# SCH_Smart_Home_2023-06-21.net
KiCad netlist of a schematic drawn in EasyEDA
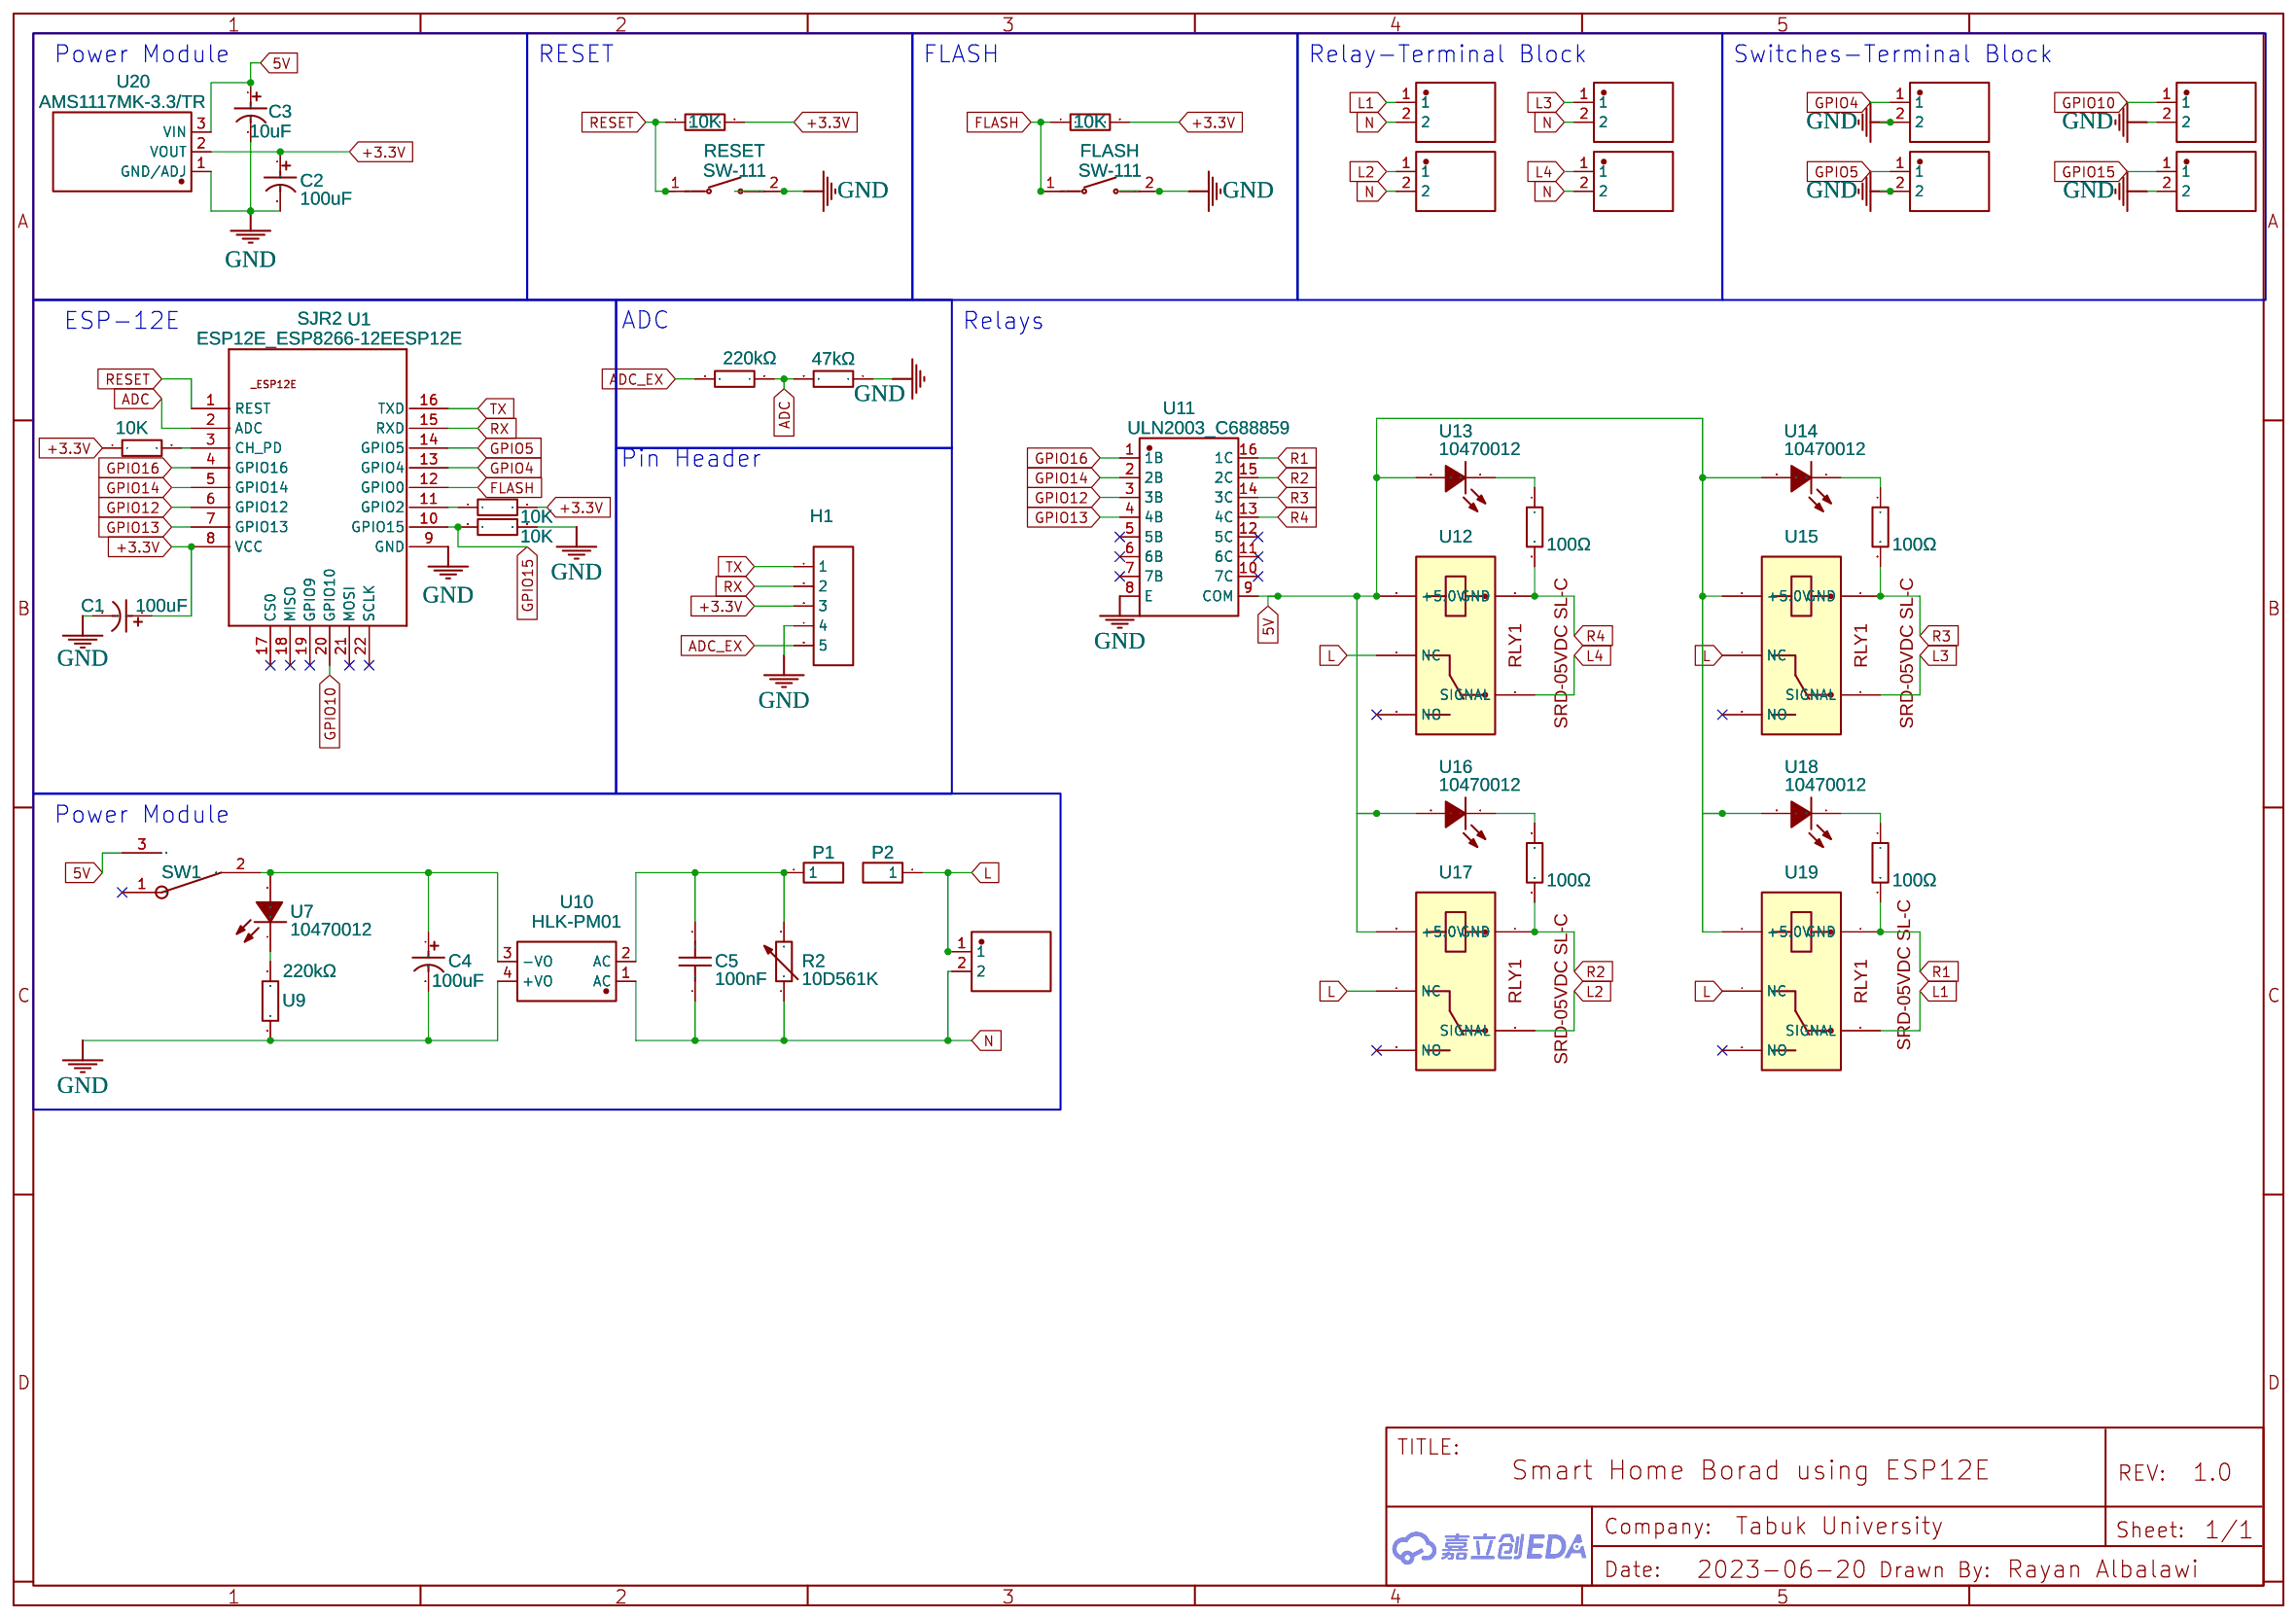
[diagram p0: schematic sheet]

(export (version "E")
  (design (tool "Eeschema 10.0.6"))
  (components
    (comp (ref "C1")
      (value "100uF")
      (fields
        (field (name "BOM_Manufacturer Part") "100uF 35V 6.3*11")
        (field (name "BOM_Supplier Part") "C45076")
      )
      (libsource (lib "") (part "100uF 35V 6.3*11_C45076_1"))
    )
    (comp (ref "C2")
      (value "100uF")
      (fields
        (field (name "BOM_Manufacturer Part") "100uF 35V 6.3*11")
        (field (name "BOM_Supplier Part") "C45076")
      )
      (libsource (lib "") (part "100uF 35V 6.3*11_C45076"))
    )
    (comp (ref "C3")
      (value "10uF")
      (fields
        (field (name "BOM_Manufacturer Part") "100uF 35V 6.3*11")
        (field (name "BOM_Supplier Part") "C45076")
      )
      (libsource (lib "") (part "100uF 35V 6.3*11_C45076"))
    )
    (comp (ref "C4")
      (value "100uF")
      (fields
        (field (name "BOM_Manufacturer Part") "100uF 35V 6.3*11")
        (field (name "BOM_Supplier Part") "C45076")
      )
      (libsource (lib "") (part "100uF 35V 6.3*11_C45076"))
    )
    (comp (ref "C5")
      (value "100nF")
      (fields
        (field (name "BOM_Manufacturer Part") "B32520C3104K000")
        (field (name "BOM_Supplier Part") "C125382")
      )
      (libsource (lib "") (part "B32520C3104K000"))
    )
    (comp (ref "CN1")
      (value "WJ127-5.0-2P_C187897")
      (fields
        (field (name "BOM_Manufacturer Part") "WJ127-5.0-2P")
        (field (name "BOM_Supplier Part") "C187897")
      )
      (libsource (lib "") (part "WJ127-5.0-2P_C187897"))
    )
    (comp (ref "CN2")
      (value "WJ127-5.0-2P_C187897")
      (fields
        (field (name "BOM_Manufacturer Part") "WJ127-5.0-2P")
        (field (name "BOM_Supplier Part") "C187897")
      )
      (libsource (lib "") (part "WJ127-5.0-2P_C187897"))
    )
    (comp (ref "CN3")
      (value "WJ127-5.0-2P_C187897")
      (fields
        (field (name "BOM_Manufacturer Part") "WJ127-5.0-2P")
        (field (name "BOM_Supplier Part") "C187897")
      )
      (libsource (lib "") (part "WJ127-5.0-2P_C187897"))
    )
    (comp (ref "CN4")
      (value "WJ127-5.0-2P_C187897")
      (fields
        (field (name "BOM_Manufacturer Part") "WJ127-5.0-2P")
        (field (name "BOM_Supplier Part") "C187897")
      )
      (libsource (lib "") (part "WJ127-5.0-2P_C187897"))
    )
    (comp (ref "CN5")
      (value "WJ127-5.0-2P_C187897")
      (fields
        (field (name "BOM_Manufacturer Part") "WJ127-5.0-2P")
        (field (name "BOM_Supplier Part") "C187897")
      )
      (libsource (lib "") (part "WJ127-5.0-2P_C187897"))
    )
    (comp (ref "CN6")
      (value "WJ127-5.0-2P_C187897")
      (fields
        (field (name "BOM_Manufacturer Part") "WJ127-5.0-2P")
        (field (name "BOM_Supplier Part") "C187897")
      )
      (libsource (lib "") (part "WJ127-5.0-2P_C187897"))
    )
    (comp (ref "CN7")
      (value "WJ127-5.0-2P_C187897")
      (fields
        (field (name "BOM_Manufacturer Part") "WJ127-5.0-2P")
        (field (name "BOM_Supplier Part") "C187897")
      )
      (libsource (lib "") (part "WJ127-5.0-2P_C187897"))
    )
    (comp (ref "CN8")
      (value "WJ127-5.0-2P_C187897")
      (fields
        (field (name "BOM_Manufacturer Part") "WJ127-5.0-2P")
        (field (name "BOM_Supplier Part") "C187897")
      )
      (libsource (lib "") (part "WJ127-5.0-2P_C187897"))
    )
    (comp (ref "CN9")
      (value "WJ127-5.0-2P_C187897")
      (fields
        (field (name "BOM_Manufacturer Part") "WJ127-5.0-2P")
        (field (name "BOM_Supplier Part") "C187897")
      )
      (libsource (lib "") (part "WJ127-5.0-2P_C187897"))
    )
    (comp (ref "FLASH")
      (value "SW-111")
      (fields (field (name "BOM_Supplier Part") "C294475"))
      (libsource (lib "") (part "SW-111"))
    )
    (comp (ref "H1")
      (value "Header-Female-2.54_1x5")
      (fields (field (name "BOM_Manufacturer Part") "2.54-1*5P母") (field (name "BOM_Supplier Part") "C50950"))
      (libsource (lib "") (part "Header-Female-2.54_1x5"))
    )
    (comp (ref "P1")
      (value "Header-Male-2.54_1x1")
      (fields (field (name "BOM_Manufacturer Part") "2.54-1*1P针") (field (name "BOM_Supplier Part") "C81276"))
      (libsource (lib "") (part "Header-Male-2.54_1x1"))
    )
    (comp (ref "P2")
      (value "Header-Male-2.54_1x1")
      (fields (field (name "BOM_Manufacturer Part") "2.54-1*1P针") (field (name "BOM_Supplier Part") "C81276"))
      (libsource (lib "") (part "Header-Male-2.54_1x1_1"))
    )
    (comp (ref "R1")
      (value "47kΩ")
      (fields
        (field (name "BOM_Manufacturer Part") "MOF2WS-47KΩ±5% T")
        (field (name "BOM_Supplier Part") "C121703")
      )
      (libsource (lib "") (part "MOF2WS-47KΩ±5% T_1"))
    )
    (comp (ref "R2")
      (value "10D561K")
      (fields (field (name "BOM_Supplier Part") "C113236"))
      (libsource (lib "") (part "10D561K"))
    )
    (comp (ref "R3")
      (value "100Ω")
      (fields
        (field (name "BOM_Manufacturer Part") "MOF2WS-47KΩ±5% T")
        (field (name "BOM_Supplier Part") "C121703")
      )
      (libsource (lib "") (part "MOF2WS-47KΩ±5% T"))
    )
    (comp (ref "R4")
      (value "100Ω")
      (fields
        (field (name "BOM_Manufacturer Part") "MOF2WS-47KΩ±5% T")
        (field (name "BOM_Supplier Part") "C121703")
      )
      (libsource (lib "") (part "MOF2WS-47KΩ±5% T"))
    )
    (comp (ref "R5")
      (value "100Ω")
      (fields
        (field (name "BOM_Manufacturer Part") "MOF2WS-47KΩ±5% T")
        (field (name "BOM_Supplier Part") "C121703")
      )
      (libsource (lib "") (part "MOF2WS-47KΩ±5% T"))
    )
    (comp (ref "R6")
      (value "100Ω")
      (fields
        (field (name "BOM_Manufacturer Part") "MOF2WS-47KΩ±5% T")
        (field (name "BOM_Supplier Part") "C121703")
      )
      (libsource (lib "") (part "MOF2WS-47KΩ±5% T"))
    )
    (comp (ref "RESET")
      (value "SW-111")
      (fields (field (name "BOM_Supplier Part") "C294475"))
      (libsource (lib "") (part "SW-111_1"))
    )
    (comp (ref "SJR2")
      (value "ESP12E_ESP8266-12EESP12E")
      (libsource (lib "") (part "ESP12E_ESP8266-12EESP12E"))
    )
    (comp (ref "SW1")
      (value "EG1218")
      (fields (field (name "BOM_Supplier Part") "C273394"))
      (libsource (lib "") (part "EG1218"))
    )
    (comp (ref "U1")
      (value "10K")
      (fields
        (field (name "BOM_Manufacturer Part") "B3950-10K 1%")
        (field (name "BOM_Supplier Part") "C9900005609")
      )
      (libsource (lib "") (part "B3950-10K 1%"))
    )
    (comp (ref "U3")
      (value "10K")
      (fields
        (field (name "BOM_Manufacturer Part") "B3950-10K 1%")
        (field (name "BOM_Supplier Part") "C9900005609")
      )
      (libsource (lib "") (part "B3950-10K 1%"))
    )
    (comp (ref "U4")
      (value "10K")
      (fields
        (field (name "BOM_Manufacturer Part") "B3950-10K 1%")
        (field (name "BOM_Supplier Part") "C9900005609")
      )
      (libsource (lib "") (part "B3950-10K 1%"))
    )
    (comp (ref "U5")
      (value "10K")
      (fields
        (field (name "BOM_Manufacturer Part") "B3950-10K 1%")
        (field (name "BOM_Supplier Part") "C9900005609")
      )
      (libsource (lib "") (part "B3950-10K 1%"))
    )
    (comp (ref "U6")
      (value "10K")
      (fields
        (field (name "BOM_Manufacturer Part") "B3950-10K 1%")
        (field (name "BOM_Supplier Part") "C9900005609")
      )
      (libsource (lib "") (part "B3950-10K 1%"))
    )
    (comp (ref "U7")
      (value "10470012")
      (fields (field (name "BOM_Supplier Part") "C9900018803"))
      (libsource (lib "") (part "10470012_1"))
    )
    (comp (ref "U8")
      (value "220kΩ")
      (fields
        (field (name "BOM_Manufacturer Part") "MOF3WS-100KΩ±5% T")
        (field (name "BOM_Supplier Part") "C121880")
      )
      (libsource (lib "") (part "MOF3WS-100KΩ±5% T_1"))
    )
    (comp (ref "U9")
      (value "220kΩ")
      (fields
        (field (name "BOM_Manufacturer Part") "MOF3WS-100KΩ±5% T")
        (field (name "BOM_Supplier Part") "C121880")
      )
      (libsource (lib "") (part "MOF3WS-100KΩ±5% T"))
    )
    (comp (ref "U10")
      (value "HLK-PM01")
      (fields (field (name "BOM_Supplier Part") "C209903"))
      (libsource (lib "") (part "HLK-PM01"))
    )
    (comp (ref "U11")
      (value "ULN2003_C688859")
      (fields (field (name "BOM_Manufacturer Part") "ULN2003") (field (name "BOM_Supplier Part") "C688859"))
      (libsource (lib "") (part "ULN2003_C688859"))
    )
    (comp (ref "U12")
      (value "SRD-05VDC SL-C BY JMAD COPY")
      (fields (field (name "BOM_Supplier Part") "SRD-05VDC SL-C"))
      (libsource (lib "") (part "SRD-05VDC SL-C BY JMAD COPY"))
    )
    (comp (ref "U13")
      (value "10470012")
      (fields (field (name "BOM_Supplier Part") "C9900018803"))
      (libsource (lib "") (part "10470012"))
    )
    (comp (ref "U14")
      (value "10470012")
      (fields (field (name "BOM_Supplier Part") "C9900018803"))
      (libsource (lib "") (part "10470012"))
    )
    (comp (ref "U15")
      (value "SRD-05VDC SL-C BY JMAD COPY")
      (fields (field (name "BOM_Supplier Part") "SRD-05VDC SL-C"))
      (libsource (lib "") (part "SRD-05VDC SL-C BY JMAD COPY"))
    )
    (comp (ref "U16")
      (value "10470012")
      (fields (field (name "BOM_Supplier Part") "C9900018803"))
      (libsource (lib "") (part "10470012"))
    )
    (comp (ref "U17")
      (value "SRD-05VDC SL-C BY JMAD COPY")
      (fields (field (name "BOM_Supplier Part") "SRD-05VDC SL-C"))
      (libsource (lib "") (part "SRD-05VDC SL-C BY JMAD COPY"))
    )
    (comp (ref "U18")
      (value "10470012")
      (fields (field (name "BOM_Supplier Part") "C9900018803"))
      (libsource (lib "") (part "10470012"))
    )
    (comp (ref "U19")
      (value "SRD-05VDC SL-C BY JMAD COPY")
      (fields (field (name "BOM_Supplier Part") "SRD-05VDC SL-C"))
      (libsource (lib "") (part "SRD-05VDC SL-C BY JMAD COPY_1"))
    )
    (comp (ref "U20")
      (value "AMS1117MK-3.3/TR")
      (fields (field (name "BOM_Supplier Part") "C498147"))
      (libsource (lib "") (part "AMS1117MK-3.3/TR"))
    )
  )
  (nets
    (net (code "1") (name "+3.3V") (class "Default")
      (node (ref "C1") (pin "1") (pinfunction "1_1") (pintype "input"))
      (node (ref "C2") (pin "1") (pinfunction "1_1") (pintype "input"))
      (node (ref "H1") (pin "3") (pinfunction "3_3") (pintype "input"))
      (node (ref "SJR2") (pin "8") (pinfunction "VCC_8") (pintype "bidirectional"))
      (node (ref "U1") (pin "1") (pinfunction "1_1") (pintype "unspecified"))
      (node (ref "U20") (pin "2") (pinfunction "VOUT_2") (pintype "unspecified"))
      (node (ref "U3") (pin "2") (pinfunction "2_2") (pintype "unspecified"))
      (node (ref "U5") (pin "2") (pinfunction "2_2") (pintype "unspecified"))
      (node (ref "U6") (pin "2") (pinfunction "2_2") (pintype "unspecified"))
    )
    (net (code "2") (name "5V") (class "Default")
      (node (ref "C3") (pin "1") (pinfunction "1_1") (pintype "input"))
      (node (ref "SW1") (pin "3") (pinfunction "3_3") (pintype "input"))
      (node (ref "U11") (pin "9") (pinfunction "COM_9") (pintype "unspecified"))
      (node (ref "U12") (pin "2") (pinfunction "+5.0V_2") (pintype "passive"))
      (node (ref "U13") (pin "2") (pinfunction "A_2") (pintype "unspecified"))
      (node (ref "U14") (pin "2") (pinfunction "A_2") (pintype "unspecified"))
      (node (ref "U15") (pin "2") (pinfunction "+5.0V_2") (pintype "passive"))
      (node (ref "U16") (pin "2") (pinfunction "A_2") (pintype "unspecified"))
      (node (ref "U17") (pin "2") (pinfunction "+5.0V_2") (pintype "passive"))
      (node (ref "U18") (pin "2") (pinfunction "A_2") (pintype "unspecified"))
      (node (ref "U19") (pin "2") (pinfunction "+5.0V_2") (pintype "passive"))
      (node (ref "U20") (pin "3") (pinfunction "VIN_3") (pintype "unspecified"))
    )
    (net (code "3") (name "ADC") (class "Default")
      (node (ref "R1") (pin "2") (pinfunction "2_2") (pintype "unspecified"))
      (node (ref "SJR2") (pin "2") (pinfunction "ADC_2") (pintype "bidirectional"))
      (node (ref "U8") (pin "1") (pinfunction "1_1") (pintype "unspecified"))
    )
    (net (code "4") (name "ADC_EX") (class "Default")
      (node (ref "H1") (pin "5") (pinfunction "5_5") (pintype "input"))
      (node (ref "U8") (pin "2") (pinfunction "2_2") (pintype "unspecified"))
    )
    (net (code "5") (name "FLASH") (class "Default")
      (node (ref "FLASH") (pin "1") (pinfunction "1_1") (pintype "unspecified"))
      (node (ref "SJR2") (pin "12") (pinfunction "GPIO0_12") (pintype "bidirectional"))
      (node (ref "U6") (pin "1") (pinfunction "1_1") (pintype "unspecified"))
    )
    (net (code "6") (name "GND") (class "Default")
      (node (ref "C1") (pin "2") (pinfunction "2_2") (pintype "input"))
      (node (ref "C2") (pin "2") (pinfunction "2_2") (pintype "input"))
      (node (ref "C3") (pin "2") (pinfunction "2_2") (pintype "input"))
      (node (ref "C4") (pin "2") (pinfunction "2_2") (pintype "input"))
      (node (ref "CN5") (pin "2") (pinfunction "2_2") (pintype "unspecified"))
      (node (ref "CN6") (pin "2") (pinfunction "2_2") (pintype "unspecified"))
      (node (ref "CN7") (pin "2") (pinfunction "2_2") (pintype "unspecified"))
      (node (ref "CN8") (pin "2") (pinfunction "2_2") (pintype "unspecified"))
      (node (ref "FLASH") (pin "2") (pinfunction "2_2") (pintype "unspecified"))
      (node (ref "H1") (pin "4") (pinfunction "4_4") (pintype "input"))
      (node (ref "R1") (pin "1") (pinfunction "1_1") (pintype "unspecified"))
      (node (ref "RESET") (pin "2") (pinfunction "2_2") (pintype "unspecified"))
      (node (ref "SJR2") (pin "9") (pinfunction "GND_9") (pintype "bidirectional"))
      (node (ref "U10") (pin "4") (pinfunction "+VO_4") (pintype "unspecified"))
      (node (ref "U11") (pin "8") (pinfunction "E_8") (pintype "unspecified"))
      (node (ref "U20") (pin "1") (pinfunction "GND/ADJ_1") (pintype "unspecified"))
      (node (ref "U4") (pin "2") (pinfunction "2_2") (pintype "unspecified"))
      (node (ref "U9") (pin "1") (pinfunction "1_1") (pintype "unspecified"))
    )
    (net (code "7") (name "GPIO4") (class "Default")
      (node (ref "CN8") (pin "1") (pinfunction "1_1") (pintype "unspecified"))
      (node (ref "SJR2") (pin "13") (pinfunction "GPIO4_13") (pintype "bidirectional"))
    )
    (net (code "8") (name "GPIO5") (class "Default")
      (node (ref "CN7") (pin "1") (pinfunction "1_1") (pintype "unspecified"))
      (node (ref "SJR2") (pin "14") (pinfunction "GPIO5_14") (pintype "bidirectional"))
    )
    (net (code "9") (name "GPIO10") (class "Default")
      (node (ref "CN6") (pin "1") (pinfunction "1_1") (pintype "unspecified"))
      (node (ref "SJR2") (pin "20") (pinfunction "GPIO10_20") (pintype "bidirectional"))
    )
    (net (code "10") (name "GPIO12") (class "Default")
      (node (ref "SJR2") (pin "6") (pinfunction "GPIO12_6") (pintype "bidirectional"))
      (node (ref "U11") (pin "3") (pinfunction "3B_3") (pintype "unspecified"))
    )
    (net (code "11") (name "GPIO13") (class "Default")
      (node (ref "SJR2") (pin "7") (pinfunction "GPIO13_7") (pintype "bidirectional"))
      (node (ref "U11") (pin "4") (pinfunction "4B_4") (pintype "unspecified"))
    )
    (net (code "12") (name "GPIO14") (class "Default")
      (node (ref "SJR2") (pin "5") (pinfunction "GPIO14_5") (pintype "bidirectional"))
      (node (ref "U11") (pin "2") (pinfunction "2B_2") (pintype "unspecified"))
    )
    (net (code "13") (name "GPIO15") (class "Default")
      (node (ref "CN5") (pin "1") (pinfunction "1_1") (pintype "unspecified"))
      (node (ref "SJR2") (pin "10") (pinfunction "GPIO15_10") (pintype "bidirectional"))
      (node (ref "U4") (pin "1") (pinfunction "1_1") (pintype "unspecified"))
    )
    (net (code "14") (name "GPIO16") (class "Default")
      (node (ref "SJR2") (pin "4") (pinfunction "GPIO16_4") (pintype "bidirectional"))
      (node (ref "U11") (pin "1") (pinfunction "1B_1") (pintype "unspecified"))
    )
    (net (code "15") (name "L") (class "Default")
      (node (ref "CN9") (pin "1") (pinfunction "1_1") (pintype "unspecified"))
      (node (ref "P2") (pin "1") (pinfunction "1_1") (pintype "input"))
      (node (ref "U12") (pin "4") (pinfunction "NC_4") (pintype "input"))
      (node (ref "U15") (pin "4") (pinfunction "NC_4") (pintype "input"))
      (node (ref "U17") (pin "4") (pinfunction "NC_4") (pintype "input"))
      (node (ref "U19") (pin "4") (pinfunction "NC_4") (pintype "input"))
    )
    (net (code "16") (name "L1") (class "Default")
      (node (ref "CN1") (pin "1") (pinfunction "1_1") (pintype "unspecified"))
      (node (ref "U19") (pin "5") (pinfunction "SIGNAL_5") (pintype "output"))
    )
    (net (code "17") (name "L2") (class "Default")
      (node (ref "CN2") (pin "1") (pinfunction "1_1") (pintype "unspecified"))
      (node (ref "U17") (pin "5") (pinfunction "SIGNAL_5") (pintype "output"))
    )
    (net (code "18") (name "L3") (class "Default")
      (node (ref "CN3") (pin "1") (pinfunction "1_1") (pintype "unspecified"))
      (node (ref "U15") (pin "5") (pinfunction "SIGNAL_5") (pintype "output"))
    )
    (net (code "19") (name "L4") (class "Default")
      (node (ref "CN4") (pin "1") (pinfunction "1_1") (pintype "unspecified"))
      (node (ref "U12") (pin "5") (pinfunction "SIGNAL_5") (pintype "output"))
    )
    (net (code "20") (name "N") (class "Default")
      (node (ref "C5") (pin "1") (pinfunction "1_1") (pintype "unspecified"))
      (node (ref "CN1") (pin "2") (pinfunction "2_2") (pintype "unspecified"))
      (node (ref "CN2") (pin "2") (pinfunction "2_2") (pintype "unspecified"))
      (node (ref "CN3") (pin "2") (pinfunction "2_2") (pintype "unspecified"))
      (node (ref "CN4") (pin "2") (pinfunction "2_2") (pintype "unspecified"))
      (node (ref "CN9") (pin "2") (pinfunction "2_2") (pintype "unspecified"))
      (node (ref "R2") (pin "1") (pinfunction "1_1") (pintype "unspecified"))
      (node (ref "U10") (pin "1") (pinfunction "AC_1") (pintype "unspecified"))
    )
    (net (code "21") (name "Net-(C5-Pad2)") (class "Default")
      (node (ref "C5") (pin "2") (pinfunction "2_2") (pintype "unspecified"))
      (node (ref "P1") (pin "1") (pinfunction "1_1") (pintype "input"))
      (node (ref "R2") (pin "2") (pinfunction "2_2") (pintype "unspecified"))
      (node (ref "U10") (pin "2") (pinfunction "AC_2") (pintype "unspecified"))
    )
    (net (code "22") (name "Net-(SJR2-CH_PD)") (class "Default")
      (node (ref "SJR2") (pin "3") (pinfunction "CH_PD_3") (pintype "bidirectional"))
      (node (ref "U1") (pin "2") (pinfunction "2_2") (pintype "unspecified"))
    )
    (net (code "23") (name "Net-(SJR2-GPIO2)") (class "Default")
      (node (ref "SJR2") (pin "11") (pinfunction "GPIO2_11") (pintype "bidirectional"))
      (node (ref "U3") (pin "1") (pinfunction "1_1") (pintype "unspecified"))
    )
    (net (code "24") (name "Net-(U7-K)") (class "Default")
      (node (ref "U7") (pin "1") (pinfunction "K_1") (pintype "unspecified"))
      (node (ref "U9") (pin "2") (pinfunction "2_2") (pintype "unspecified"))
    )
    (net (code "25") (name "Net-(U10--VO)") (class "Default")
      (node (ref "C4") (pin "1") (pinfunction "1_1") (pintype "input"))
      (node (ref "SW1") (pin "2") (pinfunction "2_2") (pintype "input"))
      (node (ref "U10") (pin "3") (pinfunction "-VO_3") (pintype "unspecified"))
      (node (ref "U7") (pin "2") (pinfunction "A_2") (pintype "unspecified"))
    )
    (net (code "26") (name "Net-(U13-K)") (class "Default")
      (node (ref "R3") (pin "1") (pinfunction "1_1") (pintype "unspecified"))
      (node (ref "U13") (pin "1") (pinfunction "K_1") (pintype "unspecified"))
    )
    (net (code "27") (name "Net-(U14-K)") (class "Default")
      (node (ref "R4") (pin "1") (pinfunction "1_1") (pintype "unspecified"))
      (node (ref "U14") (pin "1") (pinfunction "K_1") (pintype "unspecified"))
    )
    (net (code "28") (name "Net-(U16-K)") (class "Default")
      (node (ref "R5") (pin "1") (pinfunction "1_1") (pintype "unspecified"))
      (node (ref "U16") (pin "1") (pinfunction "K_1") (pintype "unspecified"))
    )
    (net (code "29") (name "Net-(U18-K)") (class "Default")
      (node (ref "R6") (pin "1") (pinfunction "1_1") (pintype "unspecified"))
      (node (ref "U18") (pin "1") (pinfunction "K_1") (pintype "unspecified"))
    )
    (net (code "30") (name "R1") (class "Default")
      (node (ref "R6") (pin "2") (pinfunction "2_2") (pintype "unspecified"))
      (node (ref "U11") (pin "16") (pinfunction "1C_16") (pintype "unspecified"))
      (node (ref "U19") (pin "1") (pinfunction "GND_1") (pintype "passive"))
    )
    (net (code "31") (name "R2") (class "Default")
      (node (ref "R5") (pin "2") (pinfunction "2_2") (pintype "unspecified"))
      (node (ref "U11") (pin "15") (pinfunction "2C_15") (pintype "unspecified"))
      (node (ref "U17") (pin "1") (pinfunction "GND_1") (pintype "passive"))
    )
    (net (code "32") (name "R3") (class "Default")
      (node (ref "R4") (pin "2") (pinfunction "2_2") (pintype "unspecified"))
      (node (ref "U11") (pin "14") (pinfunction "3C_14") (pintype "unspecified"))
      (node (ref "U15") (pin "1") (pinfunction "GND_1") (pintype "passive"))
    )
    (net (code "33") (name "R4") (class "Default")
      (node (ref "R3") (pin "2") (pinfunction "2_2") (pintype "unspecified"))
      (node (ref "U11") (pin "13") (pinfunction "4C_13") (pintype "unspecified"))
      (node (ref "U12") (pin "1") (pinfunction "GND_1") (pintype "passive"))
    )
    (net (code "34") (name "RESET") (class "Default")
      (node (ref "RESET") (pin "1") (pinfunction "1_1") (pintype "unspecified"))
      (node (ref "SJR2") (pin "1") (pinfunction "REST_1") (pintype "bidirectional"))
      (node (ref "U5") (pin "1") (pinfunction "1_1") (pintype "unspecified"))
    )
    (net (code "35") (name "RX") (class "Default")
      (node (ref "H1") (pin "2") (pinfunction "2_2") (pintype "input"))
      (node (ref "SJR2") (pin "15") (pinfunction "RXD_15") (pintype "bidirectional"))
    )
    (net (code "36") (name "TX") (class "Default")
      (node (ref "H1") (pin "1") (pinfunction "1_1") (pintype "input"))
      (node (ref "SJR2") (pin "16") (pinfunction "TXD_16") (pintype "bidirectional"))
    )
    (net (code "37") (name "unconnected-(SJR2-CS0-Pad17)") (class "Default")
      (node (ref "SJR2") (pin "17") (pinfunction "CS0_17") (pintype "bidirectional+no_connect"))
    )
    (net (code "38") (name "unconnected-(SJR2-GPIO9-Pad19)") (class "Default")
      (node (ref "SJR2") (pin "19") (pinfunction "GPIO9_19") (pintype "bidirectional+no_connect"))
    )
    (net (code "39") (name "unconnected-(SJR2-MISO-Pad18)") (class "Default")
      (node (ref "SJR2") (pin "18") (pinfunction "MISO_18") (pintype "bidirectional+no_connect"))
    )
    (net (code "40") (name "unconnected-(SJR2-MOSI-Pad21)") (class "Default")
      (node (ref "SJR2") (pin "21") (pinfunction "MOSI_21") (pintype "bidirectional+no_connect"))
    )
    (net (code "41") (name "unconnected-(SJR2-SCLK-Pad22)") (class "Default")
      (node (ref "SJR2") (pin "22") (pinfunction "SCLK_22") (pintype "bidirectional+no_connect"))
    )
    (net (code "42") (name "unconnected-(SW1-Pad1)") (class "Default")
      (node (ref "SW1") (pin "1") (pinfunction "1_1") (pintype "input+no_connect"))
    )
    (net (code "43") (name "unconnected-(U11-5B-Pad5)") (class "Default")
      (node (ref "U11") (pin "5") (pinfunction "5B_5") (pintype "unspecified+no_connect"))
    )
    (net (code "44") (name "unconnected-(U11-5C-Pad12)") (class "Default")
      (node (ref "U11") (pin "12") (pinfunction "5C_12") (pintype "unspecified+no_connect"))
    )
    (net (code "45") (name "unconnected-(U11-6B-Pad6)") (class "Default")
      (node (ref "U11") (pin "6") (pinfunction "6B_6") (pintype "unspecified+no_connect"))
    )
    (net (code "46") (name "unconnected-(U11-6C-Pad11)") (class "Default")
      (node (ref "U11") (pin "11") (pinfunction "6C_11") (pintype "unspecified+no_connect"))
    )
    (net (code "47") (name "unconnected-(U11-7B-Pad7)") (class "Default")
      (node (ref "U11") (pin "7") (pinfunction "7B_7") (pintype "unspecified+no_connect"))
    )
    (net (code "48") (name "unconnected-(U11-7C-Pad10)") (class "Default")
      (node (ref "U11") (pin "10") (pinfunction "7C_10") (pintype "unspecified+no_connect"))
    )
    (net (code "49") (name "unconnected-(U12-NO-Pad3)") (class "Default")
      (node (ref "U12") (pin "3") (pinfunction "NO_3") (pintype "output+no_connect"))
    )
    (net (code "50") (name "unconnected-(U15-NO-Pad3)") (class "Default")
      (node (ref "U15") (pin "3") (pinfunction "NO_3") (pintype "output+no_connect"))
    )
    (net (code "51") (name "unconnected-(U17-NO-Pad3)") (class "Default")
      (node (ref "U17") (pin "3") (pinfunction "NO_3") (pintype "output+no_connect"))
    )
    (net (code "52") (name "unconnected-(U19-NO-Pad3)") (class "Default")
      (node (ref "U19") (pin "3") (pinfunction "NO_3") (pintype "output+no_connect"))
    )
  )
)
